# robot.net
KiCad netlist of a schematic drawn in EAGLE
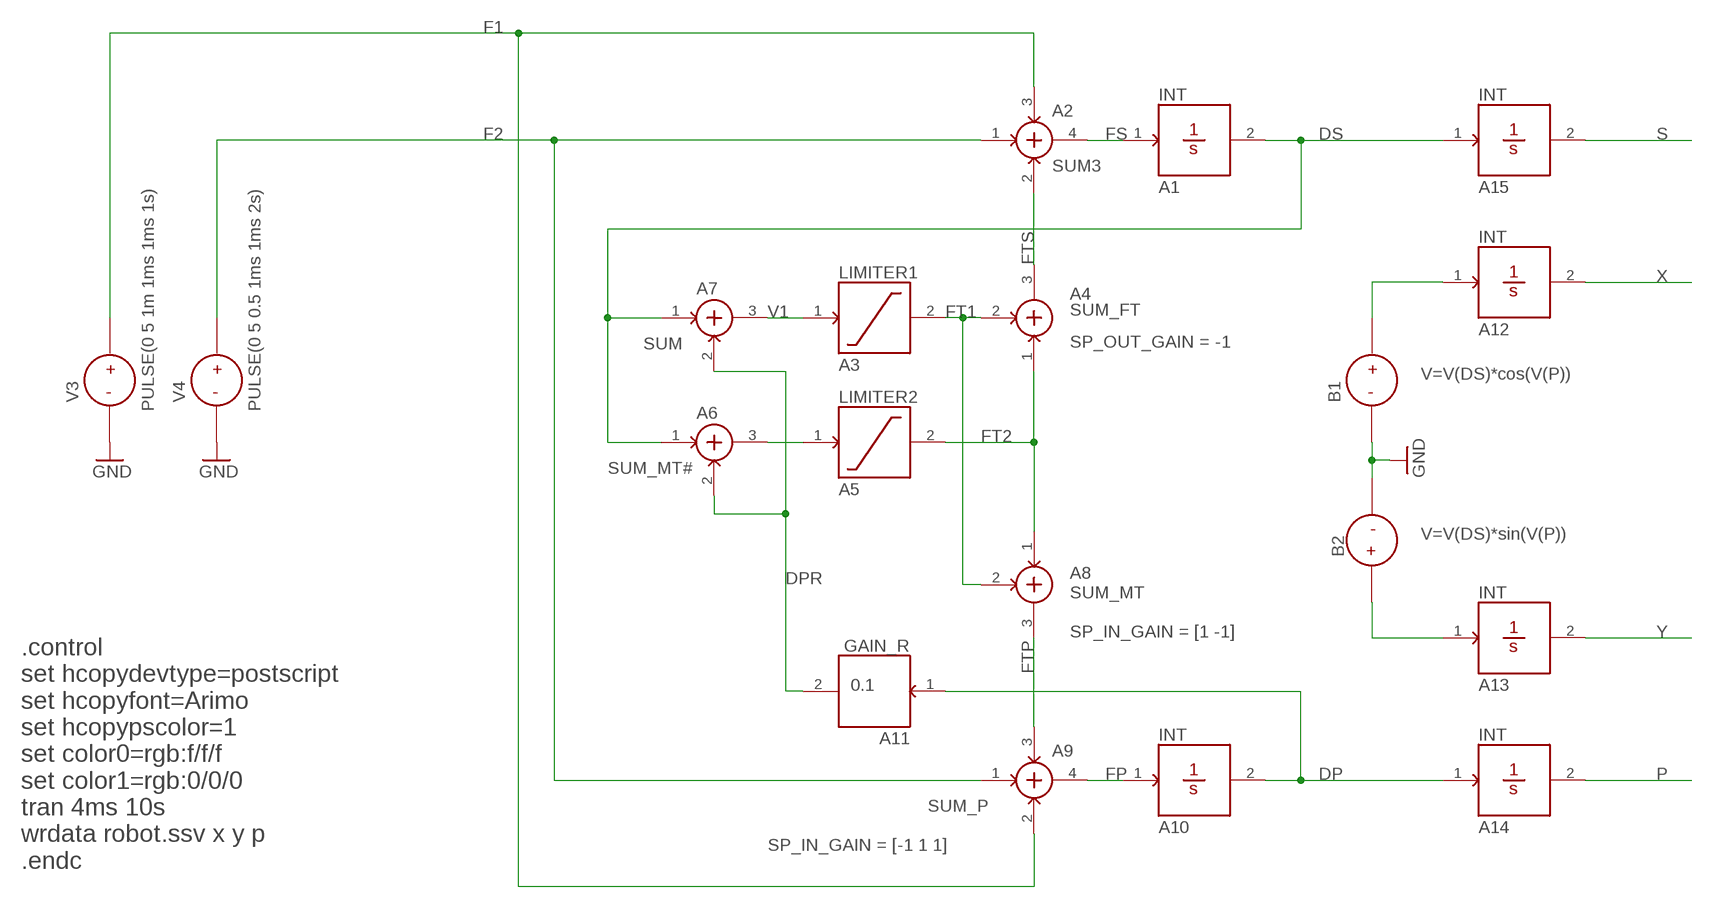
[diagram p0: schematic, sheet 1]

(export (version "E")
  (design (tool "Eeschema 10.0.6"))
  (components
    (comp (ref "A1")
      (value "INT")
      (footprint "eagle-import:SPICE2")
      (libsource (lib "eagle-import") (part "INT"))
    )
    (comp (ref "A2")
      (value "SUM3")
      (footprint "eagle-import:SPICE4")
      (libsource (lib "eagle-import") (part "SUM3"))
    )
    (comp (ref "A3")
      (value "LIMITER1")
      (footprint "eagle-import:SPICE2")
      (fields (field (name "SP_GAIN") "10") (field (name "SP_OUT_LOWER_LIMIT") "-1"))
      (libsource (lib "eagle-import") (part "LIMITER"))
    )
    (comp (ref "A4")
      (value "SUM_FT")
      (footprint "eagle-import:SPICE3")
      (fields (field (name "SP_OUT_GAIN") "1") (field (name "SP_OUT_GAIN_1") "-1"))
      (libsource (lib "eagle-import") (part "SUM"))
    )
    (comp (ref "A5")
      (value "LIMITER2")
      (footprint "eagle-import:SPICE2")
      (fields (field (name "SP_GAIN") "10") (field (name "SP_OUT_LOWER_LIMIT") "-1"))
      (libsource (lib "eagle-import") (part "LIMITER"))
    )
    (comp (ref "A6")
      (value "SUM_MT#")
      (footprint "eagle-import:SPICE3")
      (libsource (lib "eagle-import") (part "SUM"))
    )
    (comp (ref "A7")
      (value "SUM")
      (footprint "eagle-import:SPICE3")
      (libsource (lib "eagle-import") (part "SUM"))
    )
    (comp (ref "A8")
      (value "SUM_MT")
      (footprint "eagle-import:SPICE3")
      (fields (field (name "SP_IN_GAIN") "[1 1]") (field (name "SP_IN_GAIN_1") "[1 -1]"))
      (libsource (lib "eagle-import") (part "SUM"))
    )
    (comp (ref "A9")
      (value "SUM_P")
      (footprint "eagle-import:SPICE4")
      (fields (field (name "SP_IN_GAIN") "[1 1 1]") (field (name "SP_IN_GAIN_1") "[-1 1 1]"))
      (libsource (lib "eagle-import") (part "SUM3"))
    )
    (comp (ref "A10")
      (value "INT")
      (footprint "eagle-import:SPICE2")
      (libsource (lib "eagle-import") (part "INT"))
    )
    (comp (ref "A11")
      (value "GAIN_R")
      (footprint "eagle-import:SPICE2")
      (fields
        (field (name "SP_GAIN") "1")
        (field (name "SPICE_MODEL") ".model gain_r gain(in_offset gain_r out_offset)")
        (field (name "SP_GAIN_1") "0.1")
      )
      (libsource (lib "eagle-import") (part "GAIN"))
    )
    (comp (ref "A12")
      (value "INT")
      (footprint "eagle-import:SPICE2")
      (libsource (lib "eagle-import") (part "INT"))
    )
    (comp (ref "A13")
      (value "INT")
      (footprint "eagle-import:SPICE2")
      (libsource (lib "eagle-import") (part "INT"))
    )
    (comp (ref "A14")
      (value "INT")
      (footprint "eagle-import:SPICE2")
      (libsource (lib "eagle-import") (part "INT"))
    )
    (comp (ref "A15")
      (value "INT")
      (footprint "eagle-import:SPICE2")
      (libsource (lib "eagle-import") (part "INT"))
    )
    (comp (ref "B1")
      (value "V=V(DS)*cos(V(P))")
      (footprint "eagle-import:VSOURCE")
      (libsource (lib "eagle-import") (part "VSOURCE"))
    )
    (comp (ref "B2")
      (value "V=V(DS)*sin(V(P))")
      (footprint "eagle-import:VSOURCE")
      (libsource (lib "eagle-import") (part "VSOURCE"))
    )
    (comp (ref "V3")
      (value "PULSE(0 5 1m 1ms 1ms 1s)")
      (footprint "eagle-import:VSOURCE")
      (libsource (lib "eagle-import") (part "VSOURCE"))
    )
    (comp (ref "V4")
      (value "PULSE(0 5 0.5 1ms 1ms 2s)")
      (footprint "eagle-import:VSOURCE")
      (libsource (lib "eagle-import") (part "VSOURCE"))
    )
  )
  (nets
    (net (code "1") (name "/DP") (class "Default")
      (node (ref "A10") (pin "2") (pinfunction "AOUT_2") (pintype "output"))
      (node (ref "A11") (pin "1") (pinfunction "AIN_1") (pintype "input"))
      (node (ref "A14") (pin "1") (pinfunction "AIN_1") (pintype "input"))
    )
    (net (code "2") (name "/DPR") (class "Default")
      (node (ref "A11") (pin "2") (pinfunction "AOUT_2") (pintype "output"))
      (node (ref "A6") (pin "2") (pinfunction "AIN2_2") (pintype "input"))
      (node (ref "A7") (pin "2") (pinfunction "AIN2_2") (pintype "input"))
    )
    (net (code "3") (name "/DS") (class "Default")
      (node (ref "A1") (pin "2") (pinfunction "AOUT_2") (pintype "output"))
      (node (ref "A15") (pin "1") (pinfunction "AIN_1") (pintype "input"))
      (node (ref "A6") (pin "1") (pinfunction "AIN1_1") (pintype "input"))
      (node (ref "A7") (pin "1") (pinfunction "AIN1_1") (pintype "input"))
    )
    (net (code "4") (name "/F1") (class "Default")
      (node (ref "A2") (pin "3") (pinfunction "AIN3_3") (pintype "input"))
      (node (ref "A9") (pin "2") (pinfunction "AIN2_2") (pintype "input"))
      (node (ref "V3") (pin "1") (pinfunction "1_1") (pintype "output"))
    )
    (net (code "5") (name "/F2") (class "Default")
      (node (ref "A2") (pin "1") (pinfunction "AIN1_1") (pintype "input"))
      (node (ref "A9") (pin "1") (pinfunction "AIN1_1") (pintype "input"))
      (node (ref "V4") (pin "1") (pinfunction "1_1") (pintype "output"))
    )
    (net (code "6") (name "/FP") (class "Default")
      (node (ref "A10") (pin "1") (pinfunction "AIN_1") (pintype "input"))
      (node (ref "A9") (pin "4") (pinfunction "AOUT_4") (pintype "output"))
    )
    (net (code "7") (name "/FS") (class "Default")
      (node (ref "A1") (pin "1") (pinfunction "AIN_1") (pintype "input"))
      (node (ref "A2") (pin "4") (pinfunction "AOUT_4") (pintype "output"))
    )
    (net (code "8") (name "/FT1") (class "Default")
      (node (ref "A3") (pin "2") (pinfunction "AOUT_2") (pintype "output"))
      (node (ref "A4") (pin "2") (pinfunction "AIN2_2") (pintype "input"))
      (node (ref "A8") (pin "2") (pinfunction "AIN2_2") (pintype "input"))
    )
    (net (code "9") (name "/FT2") (class "Default")
      (node (ref "A4") (pin "1") (pinfunction "AIN1_1") (pintype "input"))
      (node (ref "A5") (pin "2") (pinfunction "AOUT_2") (pintype "output"))
      (node (ref "A8") (pin "1") (pinfunction "AIN1_1") (pintype "input"))
    )
    (net (code "10") (name "/FTP") (class "Default")
      (node (ref "A8") (pin "3") (pinfunction "AOUT_3") (pintype "output"))
      (node (ref "A9") (pin "3") (pinfunction "AIN3_3") (pintype "input"))
    )
    (net (code "11") (name "/FTS") (class "Default")
      (node (ref "A2") (pin "2") (pinfunction "AIN2_2") (pintype "input"))
      (node (ref "A4") (pin "3") (pinfunction "AOUT_3") (pintype "output"))
    )
    (net (code "12") (name "/P") (class "Default")
      (node (ref "A14") (pin "2") (pinfunction "AOUT_2") (pintype "output"))
    )
    (net (code "13") (name "/S") (class "Default")
      (node (ref "A15") (pin "2") (pinfunction "AOUT_2") (pintype "output"))
    )
    (net (code "14") (name "/V1") (class "Default")
      (node (ref "A3") (pin "1") (pinfunction "AIN_1") (pintype "input"))
      (node (ref "A7") (pin "3") (pinfunction "AOUT_3") (pintype "output"))
    )
    (net (code "15") (name "/X") (class "Default")
      (node (ref "A12") (pin "2") (pinfunction "AOUT_2") (pintype "output"))
    )
    (net (code "16") (name "/Y") (class "Default")
      (node (ref "A13") (pin "2") (pinfunction "AOUT_2") (pintype "output"))
    )
    (net (code "17") (name "GND") (class "Default")
      (node (ref "B1") (pin "2") (pinfunction "2_2") (pintype "output"))
      (node (ref "B2") (pin "2") (pinfunction "2_2") (pintype "output"))
      (node (ref "V3") (pin "2") (pinfunction "2_2") (pintype "output"))
      (node (ref "V4") (pin "2") (pinfunction "2_2") (pintype "output"))
    )
    (net (code "18") (name "Net-(A5-AIN)") (class "Default")
      (node (ref "A5") (pin "1") (pinfunction "AIN_1") (pintype "input"))
      (node (ref "A6") (pin "3") (pinfunction "AOUT_3") (pintype "output"))
    )
    (net (code "19") (name "Net-(A12-AIN)") (class "Default")
      (node (ref "A12") (pin "1") (pinfunction "AIN_1") (pintype "input"))
      (node (ref "B1") (pin "1") (pinfunction "1_1") (pintype "output"))
    )
    (net (code "20") (name "Net-(A13-AIN)") (class "Default")
      (node (ref "A13") (pin "1") (pinfunction "AIN_1") (pintype "input"))
      (node (ref "B2") (pin "1") (pinfunction "1_1") (pintype "output"))
    )
  )
)
